# Thermistor_Interface.net
KiCad netlist of a schematic drawn in Altium Designer
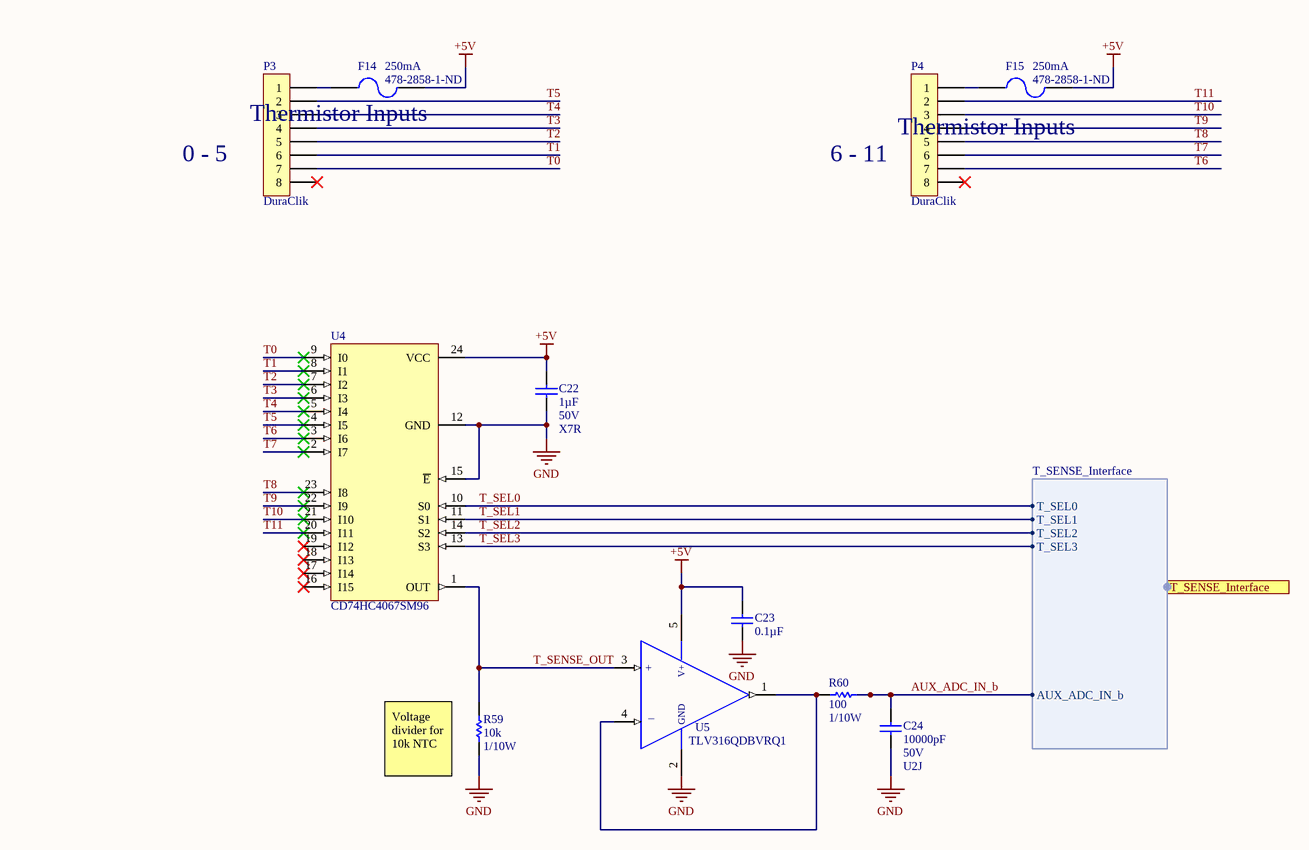
[diagram p0: Thermistor_Interface.SchDoc]

(export (version "E")
  (design (tool "Eeschema 10.0.6"))
  (components
    (comp (ref "C22")
      (value "CAP CER 1UF 50V 10% X7R 0603")
      (footprint "CAP, 0603")
      (description "1µF ±10% 50V Ceramic Capacitor X7R 0603 (1608 Metric)")
      (fields
        (field (name "TOLERANCE") "±10%")
        (field (name "CAPACITANCE") "1µF")
        (field (name "VOLTAGE") "50V")
        (field (name "TEMPERATURE COEFFICIENT") "X7R")
      )
      (libsource (lib "Schematic Diagrams") (part "CAP CER 1UF 50V 10% X7R 0603"))
    )
    (comp (ref "C23")
      (value "CAP CER 0.1UF 50V 10% X7R 0603")
      (footprint "CAP, 0603")
      (description "0.10µF ±10% 50V Ceramic Capacitor X7R 0603 (1608 Metric)")
      (fields
        (field (name "TOLERANCE") "±10%")
        (field (name "CAPACITANCE") "0.1µF")
        (field (name "VOLTAGE") "50V")
      )
      (libsource (lib "Schematic Diagrams") (part "CAP CER 0.1UF 50V 10% X7R 0603"))
    )
    (comp (ref "C24")
      (value "CAP CER 10nF 50V 5% X7R 0603")
      (footprint "CAP, 0603")
      (description "10000pF ±5% 50V Ceramic Capacitor U2J 0603 (1608 Metric)")
      (fields
        (field (name "TOLERANCE") "±5%")
        (field (name "CAPACITANCE") "10000pF")
        (field (name "VOLTAGE") "50V")
        (field (name "TEMPERATURE COEFFICIENT") "U2J")
      )
      (libsource (lib "Schematic Diagrams") (part "CAP CER 10nF 50V 5% X7R 0603"))
    )
    (comp (ref "F14")
      (value "FUSE 250MA 32VDC 0603")
      (footprint "RES, 0603")
      (fields
        (field (name "MANUFACTURER") "Kyocera AVX")
        (field (name "MANUFACTURER PART NUMBER") "F0603E0R25FSTR")
        (field (name "FUSE CURRENT") "250mA")
        (field (name "SUPPLIER PART NUMBER 1") "478-2858-1-ND")
      )
      (libsource (lib "Schematic Diagrams") (part "FUSE 250MA 32VDC 0603"))
    )
    (comp (ref "F15")
      (value "FUSE 250MA 32VDC 0603")
      (footprint "RES, 0603")
      (fields
        (field (name "MANUFACTURER") "Kyocera AVX")
        (field (name "MANUFACTURER PART NUMBER") "F0603E0R25FSTR")
        (field (name "FUSE CURRENT") "250mA")
        (field (name "SUPPLIER PART NUMBER 1") "478-2858-1-ND")
      )
      (libsource (lib "Schematic Diagrams") (part "FUSE 250MA 32VDC 0603"))
    )
    (comp (ref "P3")
      (value "CONN 8POS DURA-CLIK 0.079\"")
      (footprint "CONN, 8POS Dura-Clik")
      (description "8 Positions Header Connector 0.079\" (2.00mm) Surface Mount Tin")
      (fields (field (name "SERIES") "DuraClik"))
      (libsource (lib "Schematic Diagrams") (part "CONN 8POS DURA-CLIK 0.079{dblquote}"))
    )
    (comp (ref "P4")
      (value "CONN 8POS DURA-CLIK 0.079\"")
      (footprint "CONN, 8POS Dura-Clik")
      (description "8 Positions Header Connector 0.079\" (2.00mm) Surface Mount Tin")
      (fields (field (name "SERIES") "DuraClik"))
      (libsource (lib "Schematic Diagrams") (part "CONN 8POS DURA-CLIK 0.079{dblquote}"))
    )
    (comp (ref "R59")
      (value "RES 10K OHM 1% 1/10W 0603")
      (footprint "RES, 0603")
      (description "RES SMD 10K OHM 1% 1/10W 0603")
      (fields
        (field (name "TOLERANCE") "±1%")
        (field (name "RESISTANCE") "10k")
        (field (name "POWER") "1/10W")
      )
      (libsource (lib "Schematic Diagrams") (part "RES 10K OHM 1% 1/10W 0603"))
    )
    (comp (ref "R60")
      (value "RES 100 OHM 1% 1/10W 0603")
      (footprint "RES, 0603")
      (description "100 Ohm ±1% 0.1W, 1/10W Chip Resistor 0603 (1608 Metric) Moisture Resistant Thick Film")
      (fields
        (field (name "TOLERANCE") "±1%")
        (field (name "RESISTANCE") "100")
        (field (name "POWER") "1/10W")
      )
      (libsource (lib "Schematic Diagrams") (part "RES 100 OHM 1% 1/10W 0603"))
    )
    (comp (ref "U4")
      (value "IC MUX/DEMUX 1X16 24SSOP")
      (footprint "SSOP-24_GN")
      (description "1 Circuit IC Switch 16:1 160 Ohm 24-SSOP")
      (fields (field (name "MANUFACTURER PART NUMBER 1") "CD74HC4067SM96"))
      (libsource (lib "Schematic Diagrams") (part "IC MUX/DEMUX 1X16 24SSOP"))
    )
    (comp (ref "U5")
      (value "IC OP AMP GEN PURPOSE RR 10MHZ SOT-23-5")
      (footprint "IC OP AMP GP RR 10MHZ SOT-23-5")
      (description "General Purpose Amplifier 1 Circuit Rail-to-Rail SOT-23-5")
      (fields (field (name "MANUFACTURER PART NUMBER 1") "TLV316QDBVRQ1"))
      (libsource (lib "Schematic Diagrams") (part "IC OP AMP GEN PURPOSE RR 10MHZ SOT-23-5"))
    )
  )
  (nets
    (net (code "2") (name "+5V") (class "Default")
      (node (ref "C22") (pin "1") (pinfunction "1_1") (pintype "passive"))
      (node (ref "C23") (pin "1") (pinfunction "1_1") (pintype "passive"))
      (node (ref "F14") (pin "2") (pinfunction "2_2") (pintype "passive"))
      (node (ref "F15") (pin "2") (pinfunction "2_2") (pintype "passive"))
      (node (ref "U4") (pin "24") (pinfunction "VCC_24") (pintype "power_in"))
      (node (ref "U5") (pin "5") (pinfunction "VDD_5") (pintype "power_in"))
    )
    (net (code "3") (name "/AUX_ADC_IN_b") (class "Default")
      (node (ref "C24") (pin "1") (pinfunction "1_1") (pintype "passive"))
      (node (ref "R60") (pin "2") (pinfunction "2_2") (pintype "passive"))
    )
    (net (code "4") (name "/T0") (class "Default")
      (node (ref "P3") (pin "7") (pinfunction "7_7") (pintype "passive"))
      (node (ref "U4") (pin "9") (pinfunction "I0_9") (pintype "input"))
    )
    (net (code "5") (name "/T1") (class "Default")
      (node (ref "P3") (pin "6") (pinfunction "6_6") (pintype "passive"))
      (node (ref "U4") (pin "8") (pinfunction "I1_8") (pintype "input"))
    )
    (net (code "6") (name "/T2") (class "Default")
      (node (ref "P3") (pin "5") (pinfunction "5_5") (pintype "passive"))
      (node (ref "U4") (pin "7") (pinfunction "I2_7") (pintype "input"))
    )
    (net (code "7") (name "/T3") (class "Default")
      (node (ref "P3") (pin "4") (pinfunction "4_4") (pintype "passive"))
      (node (ref "U4") (pin "6") (pinfunction "I3_6") (pintype "input"))
    )
    (net (code "8") (name "/T4") (class "Default")
      (node (ref "P3") (pin "3") (pinfunction "3_3") (pintype "passive"))
      (node (ref "U4") (pin "5") (pinfunction "I4_5") (pintype "input"))
    )
    (net (code "9") (name "/T5") (class "Default")
      (node (ref "P3") (pin "2") (pinfunction "2_2") (pintype "passive"))
      (node (ref "U4") (pin "4") (pinfunction "I5_4") (pintype "input"))
    )
    (net (code "10") (name "/T6") (class "Default")
      (node (ref "P4") (pin "7") (pinfunction "7_7") (pintype "passive"))
      (node (ref "U4") (pin "3") (pinfunction "I6_3") (pintype "input"))
    )
    (net (code "11") (name "/T7") (class "Default")
      (node (ref "P4") (pin "6") (pinfunction "6_6") (pintype "passive"))
      (node (ref "U4") (pin "2") (pinfunction "I7_2") (pintype "input"))
    )
    (net (code "12") (name "/T8") (class "Default")
      (node (ref "P4") (pin "5") (pinfunction "5_5") (pintype "passive"))
      (node (ref "U4") (pin "23") (pinfunction "I8_23") (pintype "input"))
    )
    (net (code "13") (name "/T9") (class "Default")
      (node (ref "P4") (pin "4") (pinfunction "4_4") (pintype "passive"))
      (node (ref "U4") (pin "22") (pinfunction "I9_22") (pintype "input"))
    )
    (net (code "14") (name "/T10") (class "Default")
      (node (ref "P4") (pin "3") (pinfunction "3_3") (pintype "passive"))
      (node (ref "U4") (pin "21") (pinfunction "I10_21") (pintype "input"))
    )
    (net (code "15") (name "/T11") (class "Default")
      (node (ref "P4") (pin "2") (pinfunction "2_2") (pintype "passive"))
      (node (ref "U4") (pin "20") (pinfunction "I11_20") (pintype "input"))
    )
    (net (code "16") (name "/T_SEL0") (class "Default")
      (node (ref "U4") (pin "10") (pinfunction "S0_10") (pintype "input"))
    )
    (net (code "17") (name "/T_SEL1") (class "Default")
      (node (ref "U4") (pin "11") (pinfunction "S1_11") (pintype "input"))
    )
    (net (code "18") (name "/T_SEL2") (class "Default")
      (node (ref "U4") (pin "14") (pinfunction "S2_14") (pintype "input"))
    )
    (net (code "19") (name "/T_SEL3") (class "Default")
      (node (ref "U4") (pin "13") (pinfunction "S3_13") (pintype "input"))
    )
    (net (code "20") (name "/T_SENSE_OUT") (class "Default")
      (node (ref "R59") (pin "1") (pinfunction "1_1") (pintype "passive"))
      (node (ref "U4") (pin "1") (pinfunction "OUT_1") (pintype "output"))
      (node (ref "U5") (pin "3") (pinfunction "+IN_3") (pintype "input"))
    )
    (net (code "22") (name "GND") (class "Default")
      (node (ref "C22") (pin "2") (pinfunction "2_2") (pintype "passive"))
      (node (ref "C23") (pin "2") (pinfunction "2_2") (pintype "passive"))
      (node (ref "C24") (pin "2") (pinfunction "2_2") (pintype "passive"))
      (node (ref "R59") (pin "2") (pinfunction "2_2") (pintype "passive"))
      (node (ref "U4") (pin "12") (pinfunction "GND_12") (pintype "power_in"))
      (node (ref "U4") (pin "15") (pinfunction "~{E}_15") (pintype "input"))
      (node (ref "U5") (pin "2") (pinfunction "VSS_2") (pintype "power_in"))
    )
    (net (code "23") (name "Net-(F14-Pad1)") (class "Default")
      (node (ref "F14") (pin "1") (pinfunction "1_1") (pintype "passive"))
      (node (ref "P3") (pin "1") (pinfunction "1_1") (pintype "passive"))
    )
    (net (code "24") (name "Net-(F15-Pad1)") (class "Default")
      (node (ref "F15") (pin "1") (pinfunction "1_1") (pintype "passive"))
      (node (ref "P4") (pin "1") (pinfunction "1_1") (pintype "passive"))
    )
    (net (code "25") (name "Net-(U5--IN)") (class "Default")
      (node (ref "R60") (pin "1") (pinfunction "1_1") (pintype "passive"))
      (node (ref "U5") (pin "1") (pinfunction "OUTPUT_1") (pintype "output"))
      (node (ref "U5") (pin "4") (pinfunction "-IN_4") (pintype "input"))
    )
    (net (code "26") (name "unconnected-(P3-Pad8)") (class "Default")
      (node (ref "P3") (pin "8") (pinfunction "8_8") (pintype "passive+no_connect"))
    )
    (net (code "27") (name "unconnected-(P4-Pad8)") (class "Default")
      (node (ref "P4") (pin "8") (pinfunction "8_8") (pintype "passive+no_connect"))
    )
    (net (code "28") (name "unconnected-(U4-I12-Pad19)") (class "Default")
      (node (ref "U4") (pin "19") (pinfunction "I12_19") (pintype "input+no_connect"))
    )
    (net (code "29") (name "unconnected-(U4-I13-Pad18)") (class "Default")
      (node (ref "U4") (pin "18") (pinfunction "I13_18") (pintype "input+no_connect"))
    )
    (net (code "30") (name "unconnected-(U4-I14-Pad17)") (class "Default")
      (node (ref "U4") (pin "17") (pinfunction "I14_17") (pintype "input+no_connect"))
    )
    (net (code "31") (name "unconnected-(U4-I15-Pad16)") (class "Default")
      (node (ref "U4") (pin "16") (pinfunction "I15_16") (pintype "input+no_connect"))
    )
  )
)
